# -20220817.net
KiCad netlist of a schematic drawn in Altium Designer
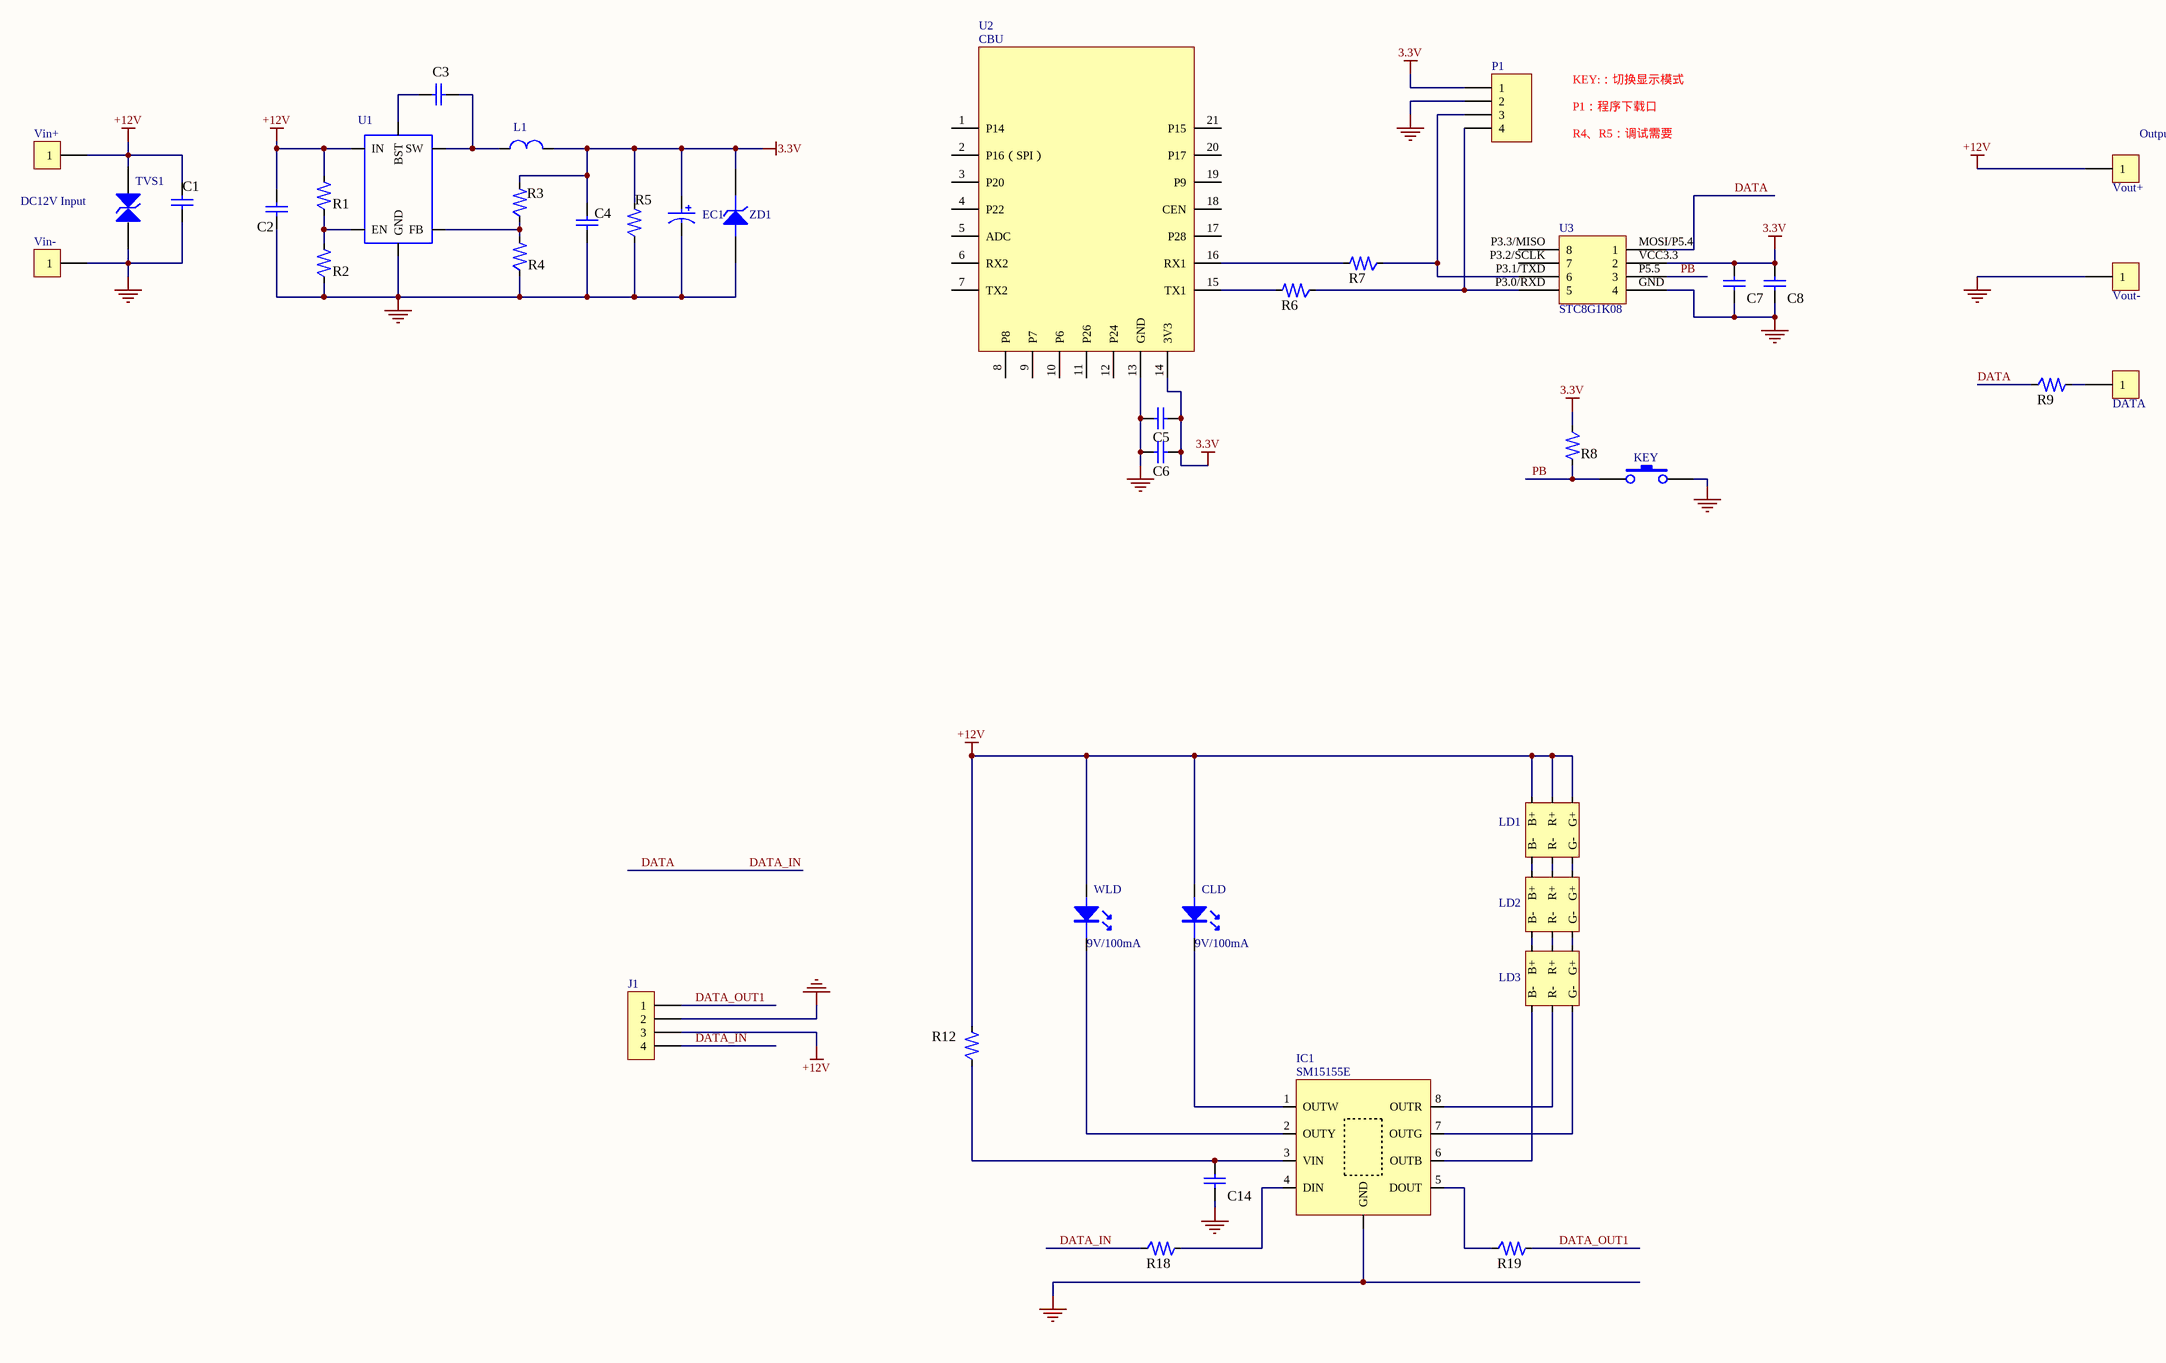
[diagram p0: 涂鸦灯串-20220817.SchDoc]

(export (version "E")
  (design (tool "Eeschema 10.0.6"))
  (components
    (comp (ref "C1")
      (value "1206")
      (footprint "JR-1206-HC")
      (description "Ceramic Capacitor")
      (libsource (lib "*") (part "Cap SMT"))
    )
    (comp (ref "C2")
      (value "1206")
      (footprint "JR-1206-HC")
      (description "Ceramic Capacitor")
      (libsource (lib "*") (part "Cap SMT"))
    )
    (comp (ref "C3")
      (value "0805")
      (footprint "JR-0805-HC")
      (description "Ceramic Capacitor")
      (libsource (lib "*") (part "Cap SMT"))
    )
    (comp (ref "C4")
      (value "0805")
      (footprint "JR-0805-HC")
      (description "Ceramic Capacitor")
      (libsource (lib "*") (part "Cap SMT"))
    )
    (comp (ref "C5")
      (value "0805")
      (footprint "JR-0805-HC")
      (description "Ceramic Capacitor")
      (libsource (lib "*") (part "Cap SMT"))
    )
    (comp (ref "C6")
      (value "0805")
      (footprint "JR-0805-HC")
      (description "Ceramic Capacitor")
      (libsource (lib "*") (part "Cap SMT"))
    )
    (comp (ref "C7")
      (value "0805")
      (footprint "JR-0805-HC")
      (description "Ceramic Capacitor")
      (libsource (lib "") (part "Cap SMT_1"))
    )
    (comp (ref "C8")
      (value "0805")
      (footprint "JR-0805-HC")
      (description "Ceramic Capacitor")
      (libsource (lib "") (part "Cap SMT_1"))
    )
    (comp (ref "C14")
      (value "1206")
      (footprint "JR-1206-HC")
      (description "Ceramic Capacitor")
      (libsource (lib "*") (part "Cap SMT"))
    )
    (comp (ref "CLD")
      (value "9V/100mA")
      (footprint "2835 LED-APT - CW")
      (libsource (lib "Sam's SCH Library") (part "LED"))
    )
    (comp (ref "DATA")
      (value "CON1")
      (footprint "电线焊盘-1")
      (description "Connector")
      (libsource (lib "") (part "CON1_1"))
    )
    (comp (ref "EC1") (value "5*11") (footprint "JR-Φ6.3*11mm电解电容-3D") (libsource (lib "*") (part "ELECTRO")))
    (comp (ref "IC1")
      (value "SM15155E")
      (footprint "ESOP-8-3D")
      (libsource (lib "Sam's SCH Library") (part "SM15155E"))
    )
    (comp (ref "J1")
      (value "CON4")
      (description "Connector")
      (libsource (lib "Sam's SCH Library") (part "CON4"))
    )
    (comp (ref "KEY")
      (value "SW-PB")
      (footprint "6*6*15轻触开关-贴片")
      (libsource (lib "Sam's SCH Library") (part "SW-PB"))
    )
    (comp (ref "L1") (value "TRANSM") (footprint "VCD54") (libsource (lib "PCB_Project1") (part "TRANSM")))
    (comp (ref "LD1")
      (value "RGB 3528")
      (footprint "Elega-2835-RGB-4-3D")
      (libsource (lib "Sam's SCH Library") (part "RGB 3528"))
    )
    (comp (ref "LD2")
      (value "RGB 3528")
      (footprint "Elega-2835-RGB-4-3D")
      (libsource (lib "Sam's SCH Library") (part "RGB 3528"))
    )
    (comp (ref "LD3")
      (value "RGB 3528")
      (footprint "Elega-2835-RGB-4-3D")
      (libsource (lib "Sam's SCH Library") (part "RGB 3528"))
    )
    (comp (ref "P1")
      (value "Header 4H")
      (footprint "HDR1X4H")
      (description "Header, 4-Pin, Right Angle")
      (fields (field (name "PUBLISHER") "Altium Limited"))
      (libsource (lib "Miscellaneous Connectors") (part "Header 4H"))
    )
    (comp (ref "R1") (value "0805") (footprint "JR-0805-HR") (libsource (lib "*") (part "RES_1")))
    (comp (ref "R2") (value "0805") (footprint "JR-0805-HR") (libsource (lib "*") (part "RES_1")))
    (comp (ref "R3") (value "0805") (footprint "JR-0805-HR") (libsource (lib "*") (part "RES_1")))
    (comp (ref "R4") (value "0805") (footprint "JR-0805-HR") (libsource (lib "*") (part "RES_1")))
    (comp (ref "R5") (value "0805") (footprint "JR-0805-HR") (libsource (lib "*") (part "RES_1")))
    (comp (ref "R6") (value "0805") (footprint "JR-0805-HR") (libsource (lib "*") (part "RES_1")))
    (comp (ref "R7") (value "0805") (footprint "JR-0805-HR") (libsource (lib "*") (part "RES_1")))
    (comp (ref "R8") (value "0805") (footprint "JR-0805-HR") (libsource (lib "*") (part "RES_1")))
    (comp (ref "R9") (value "0805") (footprint "JR-0805-HR") (libsource (lib "*") (part "RES_1")))
    (comp (ref "R12") (value "1206") (footprint "JR-1206-HR") (libsource (lib "*") (part "RES_1")))
    (comp (ref "R18") (value "1206") (footprint "JR-0805-HR") (libsource (lib "*") (part "RES_1")))
    (comp (ref "R19") (value "1206") (footprint "JR-0805-HR") (libsource (lib "*") (part "RES_1")))
    (comp (ref "TVS1")
      (value "~")
      (footprint "DO-214AC-W")
      (description "Zener Diode")
      (libsource (lib "Sam's SCH Library") (part "ZENER3_1"))
    )
    (comp (ref "U1")
      (value "MP2457GJ")
      (footprint "SOT23-6-3D")
      (libsource (lib "WIZ 串灯-20211215") (part "IC3"))
    )
    (comp (ref "U2") (value "CBU") (footprint "CBU") (libsource (lib "Sam's SCH Library") (part "CBU")))
    (comp (ref "U3") (value "STC8G1K08") (libsource (lib "Schlib1") (part "STC8G1K08")))
    (comp (ref "Vin+")
      (value "CON1")
      (footprint "电线焊盘-1")
      (description "Connector")
      (libsource (lib "Sam's SCH Library") (part "CON1"))
    )
    (comp (ref "Vin-")
      (value "CON1")
      (footprint "电线焊盘-1")
      (description "Connector")
      (libsource (lib "Sam's SCH Library") (part "CON1"))
    )
    (comp (ref "Vout+")
      (value "CON1")
      (footprint "电线焊盘-1")
      (description "Connector")
      (libsource (lib "") (part "CON1_1"))
    )
    (comp (ref "Vout-")
      (value "CON1")
      (footprint "电线焊盘-1")
      (description "Connector")
      (libsource (lib "") (part "CON1_1"))
    )
    (comp (ref "WLD")
      (value "9V/100mA")
      (footprint "2835 LED-APT - WW")
      (libsource (lib "Sam's SCH Library") (part "LED"))
    )
    (comp (ref "ZD1")
      (value "~")
      (footprint "SOD123")
      (description "Zener Diode")
      (libsource (lib "Sam's SCH Library") (part "ZENER3"))
    )
  )
  (nets
    (net (code "1") (name "+12V") (class "Default")
      (node (ref "C1") (pin "1") (pinfunction "1_1") (pintype "passive"))
      (node (ref "C2") (pin "1") (pinfunction "1_1") (pintype "passive"))
      (node (ref "CLD") (pin "1") (pinfunction "1_1") (pintype "passive"))
      (node (ref "J1") (pin "3") (pinfunction "3_3") (pintype "passive"))
      (node (ref "LD1") (pin "1") (pinfunction "G+_1") (pintype "passive"))
      (node (ref "LD1") (pin "2") (pinfunction "R+_2") (pintype "passive"))
      (node (ref "LD1") (pin "3") (pinfunction "B+_3") (pintype "passive"))
      (node (ref "R1") (pin "1") (pinfunction "1_1") (pintype "passive"))
      (node (ref "R12") (pin "1") (pinfunction "1_1") (pintype "passive"))
      (node (ref "TVS1") (pin "2") (pinfunction "K_2") (pintype "passive"))
      (node (ref "U1") (pin "5") (pinfunction "IN_5") (pintype "passive"))
      (node (ref "Vin+") (pin "1") (pinfunction "1_1") (pintype "passive"))
      (node (ref "Vout+") (pin "1") (pinfunction "1_1") (pintype "passive"))
      (node (ref "WLD") (pin "1") (pinfunction "1_1") (pintype "passive"))
    )
    (net (code "2") (name "/DATA") (class "Default")
      (node (ref "J1") (pin "4") (pinfunction "4_4") (pintype "passive"))
      (node (ref "R18") (pin "2") (pinfunction "2_2") (pintype "passive"))
      (node (ref "R9") (pin "2") (pinfunction "2_2") (pintype "passive"))
      (node (ref "U3") (pin "MOSI/P5.4") (pinfunction "1_MOSI/P5.4") (pintype "passive"))
    )
    (net (code "3") (name "/DATA_OUT1") (class "Default")
      (node (ref "J1") (pin "1") (pinfunction "1_1") (pintype "passive"))
      (node (ref "R19") (pin "1") (pinfunction "1_1") (pintype "passive"))
    )
    (net (code "4") (name "/PB") (class "Default")
      (node (ref "KEY") (pin "1") (pinfunction "1_1") (pintype "passive"))
      (node (ref "R8") (pin "1") (pinfunction "1_1") (pintype "passive"))
      (node (ref "U3") (pin "P5.5") (pinfunction "3_P5.5") (pintype "passive"))
    )
    (net (code "5") (name "3.3V") (class "Default")
      (node (ref "C4") (pin "2") (pinfunction "2_2") (pintype "passive"))
      (node (ref "C5") (pin "2") (pinfunction "2_2") (pintype "passive"))
      (node (ref "C6") (pin "2") (pinfunction "2_2") (pintype "passive"))
      (node (ref "C7") (pin "2") (pinfunction "2_2") (pintype "passive"))
      (node (ref "C8") (pin "2") (pinfunction "2_2") (pintype "passive"))
      (node (ref "EC1") (pin "1") (pinfunction "1_1") (pintype "passive"))
      (node (ref "L1") (pin "2") (pintype "passive"))
      (node (ref "P1") (pin "1") (pinfunction "1_1") (pintype "passive"))
      (node (ref "R3") (pin "1") (pinfunction "1_1") (pintype "passive"))
      (node (ref "R5") (pin "1") (pinfunction "1_1") (pintype "passive"))
      (node (ref "R8") (pin "2") (pinfunction "2_2") (pintype "passive"))
      (node (ref "U2") (pin "14") (pinfunction "3V3_14") (pintype "passive"))
      (node (ref "U3") (pin "VCC3.3") (pinfunction "2_VCC3.3") (pintype "passive"))
      (node (ref "ZD1") (pin "2") (pinfunction "K_2") (pintype "passive"))
    )
    (net (code "6") (name "GND") (class "Default")
      (node (ref "C1") (pin "2") (pinfunction "2_2") (pintype "passive"))
      (node (ref "C14") (pin "1") (pinfunction "1_1") (pintype "passive"))
      (node (ref "C2") (pin "2") (pinfunction "2_2") (pintype "passive"))
      (node (ref "C4") (pin "1") (pinfunction "1_1") (pintype "passive"))
      (node (ref "C5") (pin "1") (pinfunction "1_1") (pintype "passive"))
      (node (ref "C6") (pin "1") (pinfunction "1_1") (pintype "passive"))
      (node (ref "C7") (pin "1") (pinfunction "1_1") (pintype "passive"))
      (node (ref "C8") (pin "1") (pinfunction "1_1") (pintype "passive"))
      (node (ref "EC1") (pin "2") (pinfunction "2_2") (pintype "passive"))
      (node (ref "IC1") (pin "9") (pinfunction "GND_9") (pintype "passive"))
      (node (ref "J1") (pin "2") (pinfunction "2_2") (pintype "passive"))
      (node (ref "KEY") (pin "2") (pinfunction "2_2") (pintype "passive"))
      (node (ref "P1") (pin "2") (pinfunction "2_2") (pintype "passive"))
      (node (ref "R2") (pin "2") (pinfunction "2_2") (pintype "passive"))
      (node (ref "R4") (pin "2") (pinfunction "2_2") (pintype "passive"))
      (node (ref "R5") (pin "2") (pinfunction "2_2") (pintype "passive"))
      (node (ref "TVS1") (pin "1") (pinfunction "A_1") (pintype "passive"))
      (node (ref "U1") (pin "2") (pinfunction "GND_2") (pintype "passive"))
      (node (ref "U2") (pin "13") (pinfunction "GND_13") (pintype "passive"))
      (node (ref "U3") (pin "GND") (pinfunction "4_GND") (pintype "passive"))
      (node (ref "Vin-") (pin "1") (pinfunction "1_1") (pintype "passive"))
      (node (ref "Vout-") (pin "1") (pinfunction "1_1") (pintype "passive"))
      (node (ref "ZD1") (pin "1") (pinfunction "A_1") (pintype "passive"))
    )
    (net (code "7") (name "Net-(DATA-Pad1)") (class "Default")
      (node (ref "DATA") (pin "1") (pinfunction "1_1") (pintype "passive"))
      (node (ref "R9") (pin "1") (pinfunction "1_1") (pintype "passive"))
    )
    (net (code "8") (name "Net-(IC1-DIN)") (class "Default")
      (node (ref "IC1") (pin "4") (pinfunction "DIN_4") (pintype "passive"))
      (node (ref "R18") (pin "1") (pinfunction "1_1") (pintype "passive"))
    )
    (net (code "9") (name "Net-(IC1-DOUT)") (class "Default")
      (node (ref "IC1") (pin "5") (pinfunction "DOUT_5") (pintype "passive"))
      (node (ref "R19") (pin "2") (pinfunction "2_2") (pintype "passive"))
    )
    (net (code "10") (name "Net-(IC1-OUTB)") (class "Default")
      (node (ref "IC1") (pin "6") (pinfunction "OUTB_6") (pintype "passive"))
      (node (ref "LD3") (pin "4") (pinfunction "B-_4") (pintype "passive"))
    )
    (net (code "11") (name "Net-(IC1-OUTG)") (class "Default")
      (node (ref "IC1") (pin "7") (pinfunction "OUTG_7") (pintype "passive"))
      (node (ref "LD3") (pin "6") (pinfunction "G-_6") (pintype "passive"))
    )
    (net (code "12") (name "Net-(IC1-OUTR)") (class "Default")
      (node (ref "IC1") (pin "8") (pinfunction "OUTR_8") (pintype "passive"))
      (node (ref "LD3") (pin "5") (pinfunction "R-_5") (pintype "passive"))
    )
    (net (code "13") (name "Net-(IC1-OUTW)") (class "Default")
      (node (ref "CLD") (pin "2") (pinfunction "2_2") (pintype "passive"))
      (node (ref "IC1") (pin "1") (pinfunction "OUTW_1") (pintype "passive"))
    )
    (net (code "14") (name "Net-(IC1-OUTY)") (class "Default")
      (node (ref "IC1") (pin "2") (pinfunction "OUTY_2") (pintype "passive"))
      (node (ref "WLD") (pin "2") (pinfunction "2_2") (pintype "passive"))
    )
    (net (code "15") (name "Net-(IC1-VIN)") (class "Default")
      (node (ref "C14") (pin "2") (pinfunction "2_2") (pintype "passive"))
      (node (ref "IC1") (pin "3") (pinfunction "VIN_3") (pintype "passive"))
      (node (ref "R12") (pin "2") (pinfunction "2_2") (pintype "passive"))
    )
    (net (code "16") (name "Net-(LD1-B-)") (class "Default")
      (node (ref "LD1") (pin "4") (pinfunction "B-_4") (pintype "passive"))
      (node (ref "LD2") (pin "3") (pinfunction "B+_3") (pintype "passive"))
    )
    (net (code "17") (name "Net-(LD1-G-)") (class "Default")
      (node (ref "LD1") (pin "6") (pinfunction "G-_6") (pintype "passive"))
      (node (ref "LD2") (pin "1") (pinfunction "G+_1") (pintype "passive"))
    )
    (net (code "18") (name "Net-(LD1-R-)") (class "Default")
      (node (ref "LD1") (pin "5") (pinfunction "R-_5") (pintype "passive"))
      (node (ref "LD2") (pin "2") (pinfunction "R+_2") (pintype "passive"))
    )
    (net (code "19") (name "Net-(LD2-B-)") (class "Default")
      (node (ref "LD2") (pin "4") (pinfunction "B-_4") (pintype "passive"))
      (node (ref "LD3") (pin "3") (pinfunction "B+_3") (pintype "passive"))
    )
    (net (code "20") (name "Net-(LD2-G-)") (class "Default")
      (node (ref "LD2") (pin "6") (pinfunction "G-_6") (pintype "passive"))
      (node (ref "LD3") (pin "1") (pinfunction "G+_1") (pintype "passive"))
    )
    (net (code "21") (name "Net-(LD2-R-)") (class "Default")
      (node (ref "LD2") (pin "5") (pinfunction "R-_5") (pintype "passive"))
      (node (ref "LD3") (pin "2") (pinfunction "R+_2") (pintype "passive"))
    )
    (net (code "22") (name "Net-(U1-BST)") (class "Default")
      (node (ref "C3") (pin "2") (pinfunction "2_2") (pintype "passive"))
      (node (ref "U1") (pin "1") (pinfunction "BST_1") (pintype "passive"))
    )
    (net (code "23") (name "Net-(U1-EN)") (class "Default")
      (node (ref "R1") (pin "2") (pinfunction "2_2") (pintype "passive"))
      (node (ref "R2") (pin "1") (pinfunction "1_1") (pintype "passive"))
      (node (ref "U1") (pin "4") (pinfunction "EN_4") (pintype "passive"))
    )
    (net (code "24") (name "Net-(U1-FB)") (class "Default")
      (node (ref "R3") (pin "2") (pinfunction "2_2") (pintype "passive"))
      (node (ref "R4") (pin "1") (pinfunction "1_1") (pintype "passive"))
      (node (ref "U1") (pin "3") (pinfunction "FB_3") (pintype "passive"))
    )
    (net (code "25") (name "Net-(U1-SW)") (class "Default")
      (node (ref "C3") (pin "1") (pinfunction "1_1") (pintype "passive"))
      (node (ref "L1") (pin "1") (pintype "passive"))
      (node (ref "U1") (pin "6") (pinfunction "SW_6") (pintype "passive"))
    )
    (net (code "26") (name "Net-(U2-RX1)") (class "Default")
      (node (ref "R7") (pin "1") (pinfunction "1_1") (pintype "passive"))
      (node (ref "U2") (pin "16") (pinfunction "RX1_16") (pintype "passive"))
    )
    (net (code "27") (name "Net-(U2-TX1)") (class "Default")
      (node (ref "R6") (pin "1") (pinfunction "1_1") (pintype "passive"))
      (node (ref "U2") (pin "15") (pinfunction "TX1_15") (pintype "passive"))
    )
    (net (code "28") (name "Net-(U3-5)") (class "Default")
      (node (ref "P1") (pin "4") (pinfunction "4_4") (pintype "passive"))
      (node (ref "R6") (pin "2") (pinfunction "2_2") (pintype "passive"))
      (node (ref "U3") (pin "P3.0/RXD") (pinfunction "5_P3.0/RXD") (pintype "passive"))
    )
    (net (code "29") (name "Net-(U3-6)") (class "Default")
      (node (ref "P1") (pin "3") (pinfunction "3_3") (pintype "passive"))
      (node (ref "R7") (pin "2") (pinfunction "2_2") (pintype "passive"))
      (node (ref "U3") (pin "P3.1/TXD") (pinfunction "6_P3.1/TXD") (pintype "passive"))
    )
    (net (code "30") (name "unconnected-(U2-ADC-Pad5)") (class "Default")
      (node (ref "U2") (pin "5") (pinfunction "ADC_5") (pintype "passive"))
    )
    (net (code "31") (name "unconnected-(U2-CEN-Pad18)") (class "Default")
      (node (ref "U2") (pin "18") (pinfunction "CEN_18") (pintype "passive"))
    )
    (net (code "32") (name "unconnected-(U2-P6-Pad10)") (class "Default")
      (node (ref "U2") (pin "10") (pinfunction "P6_10") (pintype "passive"))
    )
    (net (code "33") (name "unconnected-(U2-P7-Pad9)") (class "Default")
      (node (ref "U2") (pin "9") (pinfunction "P7_9") (pintype "passive"))
    )
    (net (code "34") (name "unconnected-(U2-P8-Pad8)") (class "Default")
      (node (ref "U2") (pin "8") (pinfunction "P8_8") (pintype "passive"))
    )
    (net (code "35") (name "unconnected-(U2-P9-Pad19)") (class "Default")
      (node (ref "U2") (pin "19") (pinfunction "P9_19") (pintype "passive"))
    )
    (net (code "36") (name "unconnected-(U2-P14-Pad1)") (class "Default")
      (node (ref "U2") (pin "1") (pinfunction "P14_1") (pintype "passive"))
    )
    (net (code "37") (name "unconnected-(U2-P15-Pad21)") (class "Default")
      (node (ref "U2") (pin "21") (pinfunction "P15_21") (pintype "passive"))
    )
    (net (code "38") (name "unconnected-(U2-P16（SPI）-Pad2)") (class "Default")
      (node (ref "U2") (pin "2") (pinfunction "P16（SPI）_2") (pintype "passive"))
    )
    (net (code "39") (name "unconnected-(U2-P17-Pad20)") (class "Default")
      (node (ref "U2") (pin "20") (pinfunction "P17_20") (pintype "passive"))
    )
    (net (code "40") (name "unconnected-(U2-P20-Pad3)") (class "Default")
      (node (ref "U2") (pin "3") (pinfunction "P20_3") (pintype "passive"))
    )
    (net (code "41") (name "unconnected-(U2-P22-Pad4)") (class "Default")
      (node (ref "U2") (pin "4") (pinfunction "P22_4") (pintype "passive"))
    )
    (net (code "42") (name "unconnected-(U2-P24-Pad12)") (class "Default")
      (node (ref "U2") (pin "12") (pinfunction "P24_12") (pintype "passive"))
    )
    (net (code "43") (name "unconnected-(U2-P26-Pad11)") (class "Default")
      (node (ref "U2") (pin "11") (pinfunction "P26_11") (pintype "passive"))
    )
    (net (code "44") (name "unconnected-(U2-P28-Pad17)") (class "Default")
      (node (ref "U2") (pin "17") (pinfunction "P28_17") (pintype "passive"))
    )
    (net (code "45") (name "unconnected-(U2-RX2-Pad6)") (class "Default")
      (node (ref "U2") (pin "6") (pinfunction "RX2_6") (pintype "passive"))
    )
    (net (code "46") (name "unconnected-(U2-TX2-Pad7)") (class "Default")
      (node (ref "U2") (pin "7") (pinfunction "TX2_7") (pintype "passive"))
    )
    (net (code "47") (name "unconnected-(U3-7-PadP3.2{slash}SCLK)") (class "Default")
      (node (ref "U3") (pin "P3.2/SCLK") (pinfunction "7_P3.2/SCLK") (pintype "passive"))
    )
    (net (code "48") (name "unconnected-(U3-8-PadP3.3{slash}MISO)") (class "Default")
      (node (ref "U3") (pin "P3.3/MISO") (pinfunction "8_P3.3/MISO") (pintype "passive"))
    )
  )
)
